# Clamp-header.net
KiCad netlist of a schematic drawn in EAGLE
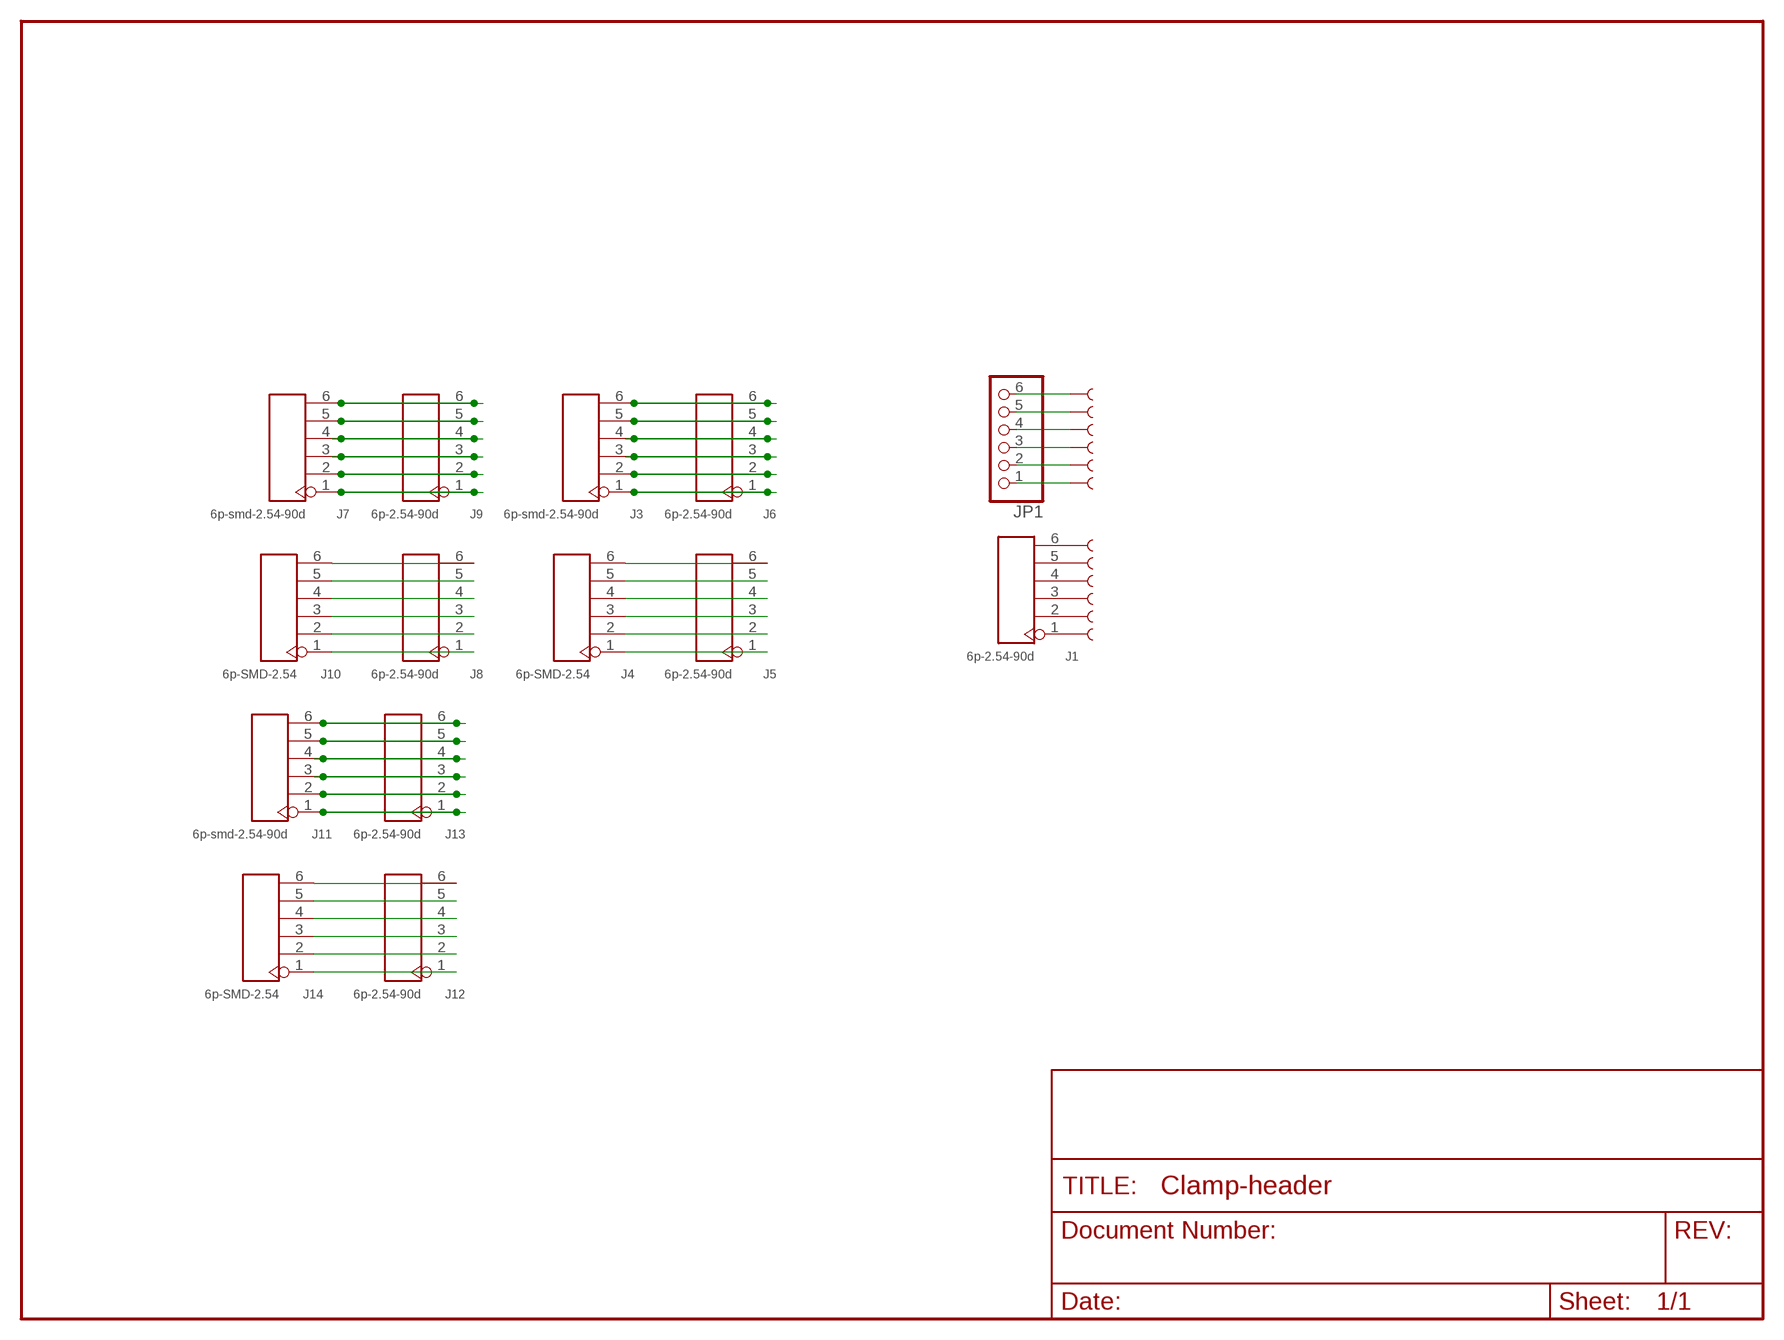
[diagram p0: schematic, sheet 1]

(export (version "E")
  (design (tool "Eeschema 10.0.6"))
  (components
    (comp (ref "J1")
      (value "6p-2.54-90d")
      (footprint "eagle-import:H6-2.54-90D-FEMALE")
      (libsource (lib "eagle-import") (part "DIP-BLACK-FEMALE-HEADER-R/A(6P-2.54-90D)"))
    )
    (comp (ref "J3")
      (value "6p-smd-2.54-90d")
      (footprint "eagle-import:H6-SMD-MALE-2.54-90D")
      (libsource (lib "eagle-import") (part "SMD-BLACK-MALE-HEADER(6P-2.54-90D)"))
    )
    (comp (ref "J4")
      (value "6p-SMD-2.54")
      (footprint "eagle-import:H6-SMD-2.54")
      (fields (field (name "MPN") "F185-1106A0BZYB1"))
      (libsource (lib "eagle-import") (part "SMD-BLACK-FEMALE-HEADER(6P-2.54)"))
    )
    (comp (ref "J5")
      (value "6p-2.54-90d")
      (footprint "eagle-import:H6-2.54-90D-FEMALE")
      (libsource (lib "eagle-import") (part "DIP-BLACK-FEMALE-HEADER-R/A(6P-2.54-90D)"))
    )
    (comp (ref "J6")
      (value "6p-2.54-90d")
      (footprint "eagle-import:H6-2.54-90D-FEMALE")
      (libsource (lib "eagle-import") (part "DIP-BLACK-FEMALE-HEADER-R/A(6P-2.54-90D)"))
    )
    (comp (ref "J7")
      (value "6p-smd-2.54-90d")
      (footprint "eagle-import:H6-SMD-MALE-2.54-90D")
      (libsource (lib "eagle-import") (part "SMD-BLACK-MALE-HEADER(6P-2.54-90D)"))
    )
    (comp (ref "J8")
      (value "6p-2.54-90d")
      (footprint "eagle-import:H6-2.54-90D-FEMALE")
      (libsource (lib "eagle-import") (part "DIP-BLACK-FEMALE-HEADER-R/A(6P-2.54-90D)"))
    )
    (comp (ref "J9")
      (value "6p-2.54-90d")
      (footprint "eagle-import:H6-2.54-90D-FEMALE")
      (libsource (lib "eagle-import") (part "DIP-BLACK-FEMALE-HEADER-R/A(6P-2.54-90D)"))
    )
    (comp (ref "J10")
      (value "6p-SMD-2.54")
      (footprint "eagle-import:H6-SMD-2.54")
      (fields (field (name "MPN") "F185-1106A0BZYB1"))
      (libsource (lib "eagle-import") (part "SMD-BLACK-FEMALE-HEADER(6P-2.54)"))
    )
    (comp (ref "J11")
      (value "6p-smd-2.54-90d")
      (footprint "eagle-import:H6-SMD-MALE-2.54-90D")
      (libsource (lib "eagle-import") (part "SMD-BLACK-MALE-HEADER(6P-2.54-90D)"))
    )
    (comp (ref "J12")
      (value "6p-2.54-90d")
      (footprint "eagle-import:H6-2.54-90D-FEMALE")
      (libsource (lib "eagle-import") (part "DIP-BLACK-FEMALE-HEADER-R/A(6P-2.54-90D)"))
    )
    (comp (ref "J13")
      (value "6p-2.54-90d")
      (footprint "eagle-import:H6-2.54-90D-FEMALE")
      (libsource (lib "eagle-import") (part "DIP-BLACK-FEMALE-HEADER-R/A(6P-2.54-90D)"))
    )
    (comp (ref "J14")
      (value "6p-SMD-2.54")
      (footprint "eagle-import:H6-SMD-2.54")
      (fields (field (name "MPN") "F185-1106A0BZYB1"))
      (libsource (lib "eagle-import") (part "SMD-BLACK-FEMALE-HEADER(6P-2.54)"))
    )
    (comp (ref "JP1")
      (value "PINHD-1X6/90")
      (footprint "eagle-import:1X06_90")
      (libsource (lib "eagle-import") (part "PINHD-1X6/90"))
    )
    (comp (ref "U$1")
      (value "SEWTAP1")
      (footprint "eagle-import:SEWTAP")
      (libsource (lib "eagle-import") (part "SEWTAP1"))
    )
    (comp (ref "U$2")
      (value "SEWTAP1")
      (footprint "eagle-import:SEWTAP")
      (libsource (lib "eagle-import") (part "SEWTAP1"))
    )
    (comp (ref "U$3")
      (value "SEWTAP1")
      (footprint "eagle-import:SEWTAP")
      (libsource (lib "eagle-import") (part "SEWTAP1"))
    )
    (comp (ref "U$4")
      (value "SEWTAP1")
      (footprint "eagle-import:SEWTAP")
      (libsource (lib "eagle-import") (part "SEWTAP1"))
    )
    (comp (ref "U$5")
      (value "SEWTAP1")
      (footprint "eagle-import:SEWTAP")
      (libsource (lib "eagle-import") (part "SEWTAP1"))
    )
    (comp (ref "U$6")
      (value "SEWTAP1")
      (footprint "eagle-import:SEWTAP")
      (libsource (lib "eagle-import") (part "SEWTAP1"))
    )
    (comp (ref "U$7")
      (value "SEWTAP1")
      (footprint "eagle-import:SEWTAP")
      (libsource (lib "eagle-import") (part "SEWTAP1"))
    )
    (comp (ref "U$35")
      (value "SEWTAP1")
      (footprint "eagle-import:SEWTAP")
      (libsource (lib "eagle-import") (part "SEWTAP1"))
    )
    (comp (ref "U$37")
      (value "SEWTAP1")
      (footprint "eagle-import:SEWTAP")
      (libsource (lib "eagle-import") (part "SEWTAP1"))
    )
    (comp (ref "U$39")
      (value "SEWTAP1")
      (footprint "eagle-import:SEWTAP")
      (libsource (lib "eagle-import") (part "SEWTAP1"))
    )
    (comp (ref "U$41")
      (value "SEWTAP1")
      (footprint "eagle-import:SEWTAP")
      (libsource (lib "eagle-import") (part "SEWTAP1"))
    )
    (comp (ref "U$51")
      (value "SEWTAP1")
      (footprint "eagle-import:SEWTAP")
      (libsource (lib "eagle-import") (part "SEWTAP1"))
    )
  )
  (nets
    (net (code "1") (name "Net-(J1-Pad1)") (class "Default")
      (node (ref "J1") (pin "1") (pinfunction "1_1") (pintype "bidirectional"))
      (node (ref "U$4") (pin "1") (pinfunction "1_1") (pintype "bidirectional"))
    )
    (net (code "2") (name "Net-(J1-Pad2)") (class "Default")
      (node (ref "J1") (pin "2") (pinfunction "2_2") (pintype "bidirectional"))
      (node (ref "U$39") (pin "1") (pinfunction "1_1") (pintype "bidirectional"))
    )
    (net (code "3") (name "Net-(J1-Pad3)") (class "Default")
      (node (ref "J1") (pin "3") (pinfunction "3_3") (pintype "bidirectional"))
      (node (ref "U$37") (pin "1") (pinfunction "1_1") (pintype "bidirectional"))
    )
    (net (code "4") (name "Net-(J1-Pad4)") (class "Default")
      (node (ref "J1") (pin "4") (pinfunction "4_4") (pintype "bidirectional"))
      (node (ref "U$35") (pin "1") (pinfunction "1_1") (pintype "bidirectional"))
    )
    (net (code "5") (name "Net-(J1-Pad5)") (class "Default")
      (node (ref "J1") (pin "5") (pinfunction "5_5") (pintype "bidirectional"))
      (node (ref "U$41") (pin "1") (pinfunction "1_1") (pintype "bidirectional"))
    )
    (net (code "6") (name "Net-(J1-Pad6)") (class "Default")
      (node (ref "J1") (pin "6") (pinfunction "6_6") (pintype "bidirectional"))
      (node (ref "U$51") (pin "1") (pinfunction "1_1") (pintype "bidirectional"))
    )
    (net (code "7") (name "Net-(J3-Pad1)") (class "Default")
      (node (ref "J3") (pin "1") (pinfunction "1_1") (pintype "bidirectional"))
      (node (ref "J6") (pin "1") (pinfunction "1_1") (pintype "bidirectional"))
    )
    (net (code "8") (name "Net-(J3-Pad2)") (class "Default")
      (node (ref "J3") (pin "2") (pinfunction "2_2") (pintype "bidirectional"))
      (node (ref "J6") (pin "2") (pinfunction "2_2") (pintype "bidirectional"))
    )
    (net (code "9") (name "Net-(J3-Pad3)") (class "Default")
      (node (ref "J3") (pin "3") (pinfunction "3_3") (pintype "bidirectional"))
      (node (ref "J6") (pin "3") (pinfunction "3_3") (pintype "bidirectional"))
    )
    (net (code "10") (name "Net-(J3-Pad4)") (class "Default")
      (node (ref "J3") (pin "4") (pinfunction "4_4") (pintype "bidirectional"))
      (node (ref "J6") (pin "4") (pinfunction "4_4") (pintype "bidirectional"))
    )
    (net (code "11") (name "Net-(J3-Pad5)") (class "Default")
      (node (ref "J3") (pin "5") (pinfunction "5_5") (pintype "bidirectional"))
      (node (ref "J6") (pin "5") (pinfunction "5_5") (pintype "bidirectional"))
    )
    (net (code "12") (name "Net-(J3-Pad6)") (class "Default")
      (node (ref "J3") (pin "6") (pinfunction "6_6") (pintype "bidirectional"))
      (node (ref "J6") (pin "6") (pinfunction "6_6") (pintype "bidirectional"))
    )
    (net (code "13") (name "Net-(J4-Pad1)") (class "Default")
      (node (ref "J4") (pin "1") (pinfunction "1_1") (pintype "bidirectional"))
      (node (ref "J5") (pin "1") (pinfunction "1_1") (pintype "bidirectional"))
    )
    (net (code "14") (name "Net-(J4-Pad2)") (class "Default")
      (node (ref "J4") (pin "2") (pinfunction "2_2") (pintype "bidirectional"))
      (node (ref "J5") (pin "2") (pinfunction "2_2") (pintype "bidirectional"))
    )
    (net (code "15") (name "Net-(J4-Pad3)") (class "Default")
      (node (ref "J4") (pin "3") (pinfunction "3_3") (pintype "bidirectional"))
      (node (ref "J5") (pin "3") (pinfunction "3_3") (pintype "bidirectional"))
    )
    (net (code "16") (name "Net-(J4-Pad4)") (class "Default")
      (node (ref "J4") (pin "4") (pinfunction "4_4") (pintype "bidirectional"))
      (node (ref "J5") (pin "4") (pinfunction "4_4") (pintype "bidirectional"))
    )
    (net (code "17") (name "Net-(J4-Pad5)") (class "Default")
      (node (ref "J4") (pin "5") (pinfunction "5_5") (pintype "bidirectional"))
      (node (ref "J5") (pin "5") (pinfunction "5_5") (pintype "bidirectional"))
    )
    (net (code "18") (name "Net-(J4-Pad6)") (class "Default")
      (node (ref "J4") (pin "6") (pinfunction "6_6") (pintype "bidirectional"))
      (node (ref "J5") (pin "6") (pinfunction "6_6") (pintype "bidirectional"))
    )
    (net (code "19") (name "Net-(J7-Pad1)") (class "Default")
      (node (ref "J7") (pin "1") (pinfunction "1_1") (pintype "bidirectional"))
      (node (ref "J9") (pin "1") (pinfunction "1_1") (pintype "bidirectional"))
    )
    (net (code "20") (name "Net-(J7-Pad2)") (class "Default")
      (node (ref "J7") (pin "2") (pinfunction "2_2") (pintype "bidirectional"))
      (node (ref "J9") (pin "2") (pinfunction "2_2") (pintype "bidirectional"))
    )
    (net (code "21") (name "Net-(J7-Pad3)") (class "Default")
      (node (ref "J7") (pin "3") (pinfunction "3_3") (pintype "bidirectional"))
      (node (ref "J9") (pin "3") (pinfunction "3_3") (pintype "bidirectional"))
    )
    (net (code "22") (name "Net-(J7-Pad4)") (class "Default")
      (node (ref "J7") (pin "4") (pinfunction "4_4") (pintype "bidirectional"))
      (node (ref "J9") (pin "4") (pinfunction "4_4") (pintype "bidirectional"))
    )
    (net (code "23") (name "Net-(J7-Pad5)") (class "Default")
      (node (ref "J7") (pin "5") (pinfunction "5_5") (pintype "bidirectional"))
      (node (ref "J9") (pin "5") (pinfunction "5_5") (pintype "bidirectional"))
    )
    (net (code "24") (name "Net-(J7-Pad6)") (class "Default")
      (node (ref "J7") (pin "6") (pinfunction "6_6") (pintype "bidirectional"))
      (node (ref "J9") (pin "6") (pinfunction "6_6") (pintype "bidirectional"))
    )
    (net (code "25") (name "Net-(J10-Pad1)") (class "Default")
      (node (ref "J10") (pin "1") (pinfunction "1_1") (pintype "bidirectional"))
      (node (ref "J8") (pin "1") (pinfunction "1_1") (pintype "bidirectional"))
    )
    (net (code "26") (name "Net-(J10-Pad2)") (class "Default")
      (node (ref "J10") (pin "2") (pinfunction "2_2") (pintype "bidirectional"))
      (node (ref "J8") (pin "2") (pinfunction "2_2") (pintype "bidirectional"))
    )
    (net (code "27") (name "Net-(J10-Pad3)") (class "Default")
      (node (ref "J10") (pin "3") (pinfunction "3_3") (pintype "bidirectional"))
      (node (ref "J8") (pin "3") (pinfunction "3_3") (pintype "bidirectional"))
    )
    (net (code "28") (name "Net-(J10-Pad4)") (class "Default")
      (node (ref "J10") (pin "4") (pinfunction "4_4") (pintype "bidirectional"))
      (node (ref "J8") (pin "4") (pinfunction "4_4") (pintype "bidirectional"))
    )
    (net (code "29") (name "Net-(J10-Pad5)") (class "Default")
      (node (ref "J10") (pin "5") (pinfunction "5_5") (pintype "bidirectional"))
      (node (ref "J8") (pin "5") (pinfunction "5_5") (pintype "bidirectional"))
    )
    (net (code "30") (name "Net-(J10-Pad6)") (class "Default")
      (node (ref "J10") (pin "6") (pinfunction "6_6") (pintype "bidirectional"))
      (node (ref "J8") (pin "6") (pinfunction "6_6") (pintype "bidirectional"))
    )
    (net (code "31") (name "Net-(J11-Pad1)") (class "Default")
      (node (ref "J11") (pin "1") (pinfunction "1_1") (pintype "bidirectional"))
      (node (ref "J13") (pin "1") (pinfunction "1_1") (pintype "bidirectional"))
    )
    (net (code "32") (name "Net-(J11-Pad2)") (class "Default")
      (node (ref "J11") (pin "2") (pinfunction "2_2") (pintype "bidirectional"))
      (node (ref "J13") (pin "2") (pinfunction "2_2") (pintype "bidirectional"))
    )
    (net (code "33") (name "Net-(J11-Pad3)") (class "Default")
      (node (ref "J11") (pin "3") (pinfunction "3_3") (pintype "bidirectional"))
      (node (ref "J13") (pin "3") (pinfunction "3_3") (pintype "bidirectional"))
    )
    (net (code "34") (name "Net-(J11-Pad4)") (class "Default")
      (node (ref "J11") (pin "4") (pinfunction "4_4") (pintype "bidirectional"))
      (node (ref "J13") (pin "4") (pinfunction "4_4") (pintype "bidirectional"))
    )
    (net (code "35") (name "Net-(J11-Pad5)") (class "Default")
      (node (ref "J11") (pin "5") (pinfunction "5_5") (pintype "bidirectional"))
      (node (ref "J13") (pin "5") (pinfunction "5_5") (pintype "bidirectional"))
    )
    (net (code "36") (name "Net-(J11-Pad6)") (class "Default")
      (node (ref "J11") (pin "6") (pinfunction "6_6") (pintype "bidirectional"))
      (node (ref "J13") (pin "6") (pinfunction "6_6") (pintype "bidirectional"))
    )
    (net (code "37") (name "Net-(J12-Pad1)") (class "Default")
      (node (ref "J12") (pin "1") (pinfunction "1_1") (pintype "bidirectional"))
      (node (ref "J14") (pin "1") (pinfunction "1_1") (pintype "bidirectional"))
    )
    (net (code "38") (name "Net-(J12-Pad2)") (class "Default")
      (node (ref "J12") (pin "2") (pinfunction "2_2") (pintype "bidirectional"))
      (node (ref "J14") (pin "2") (pinfunction "2_2") (pintype "bidirectional"))
    )
    (net (code "39") (name "Net-(J12-Pad3)") (class "Default")
      (node (ref "J12") (pin "3") (pinfunction "3_3") (pintype "bidirectional"))
      (node (ref "J14") (pin "3") (pinfunction "3_3") (pintype "bidirectional"))
    )
    (net (code "40") (name "Net-(J12-Pad4)") (class "Default")
      (node (ref "J12") (pin "4") (pinfunction "4_4") (pintype "bidirectional"))
      (node (ref "J14") (pin "4") (pinfunction "4_4") (pintype "bidirectional"))
    )
    (net (code "41") (name "Net-(J12-Pad5)") (class "Default")
      (node (ref "J12") (pin "5") (pinfunction "5_5") (pintype "bidirectional"))
      (node (ref "J14") (pin "5") (pinfunction "5_5") (pintype "bidirectional"))
    )
    (net (code "42") (name "Net-(J12-Pad6)") (class "Default")
      (node (ref "J12") (pin "6") (pinfunction "6_6") (pintype "bidirectional"))
      (node (ref "J14") (pin "6") (pinfunction "6_6") (pintype "bidirectional"))
    )
    (net (code "43") (name "Net-(JP1-Pad1)") (class "Default")
      (node (ref "JP1") (pin "1") (pinfunction "1_1") (pintype "passive"))
      (node (ref "U$2") (pin "1") (pinfunction "1_1") (pintype "bidirectional"))
    )
    (net (code "44") (name "Net-(JP1-Pad2)") (class "Default")
      (node (ref "JP1") (pin "2") (pinfunction "2_2") (pintype "passive"))
      (node (ref "U$5") (pin "1") (pinfunction "1_1") (pintype "bidirectional"))
    )
    (net (code "45") (name "Net-(JP1-Pad3)") (class "Default")
      (node (ref "JP1") (pin "3") (pinfunction "3_3") (pintype "passive"))
      (node (ref "U$1") (pin "1") (pinfunction "1_1") (pintype "bidirectional"))
    )
    (net (code "46") (name "Net-(JP1-Pad4)") (class "Default")
      (node (ref "JP1") (pin "4") (pinfunction "4_4") (pintype "passive"))
      (node (ref "U$7") (pin "1") (pinfunction "1_1") (pintype "bidirectional"))
    )
    (net (code "47") (name "Net-(JP1-Pad5)") (class "Default")
      (node (ref "JP1") (pin "5") (pinfunction "5_5") (pintype "passive"))
      (node (ref "U$6") (pin "1") (pinfunction "1_1") (pintype "bidirectional"))
    )
    (net (code "48") (name "Net-(JP1-Pad6)") (class "Default")
      (node (ref "JP1") (pin "6") (pinfunction "6_6") (pintype "passive"))
      (node (ref "U$3") (pin "1") (pinfunction "1_1") (pintype "bidirectional"))
    )
  )
)
